# PLC-_-_-V2.net
KiCad netlist of a schematic drawn in Altium Designer
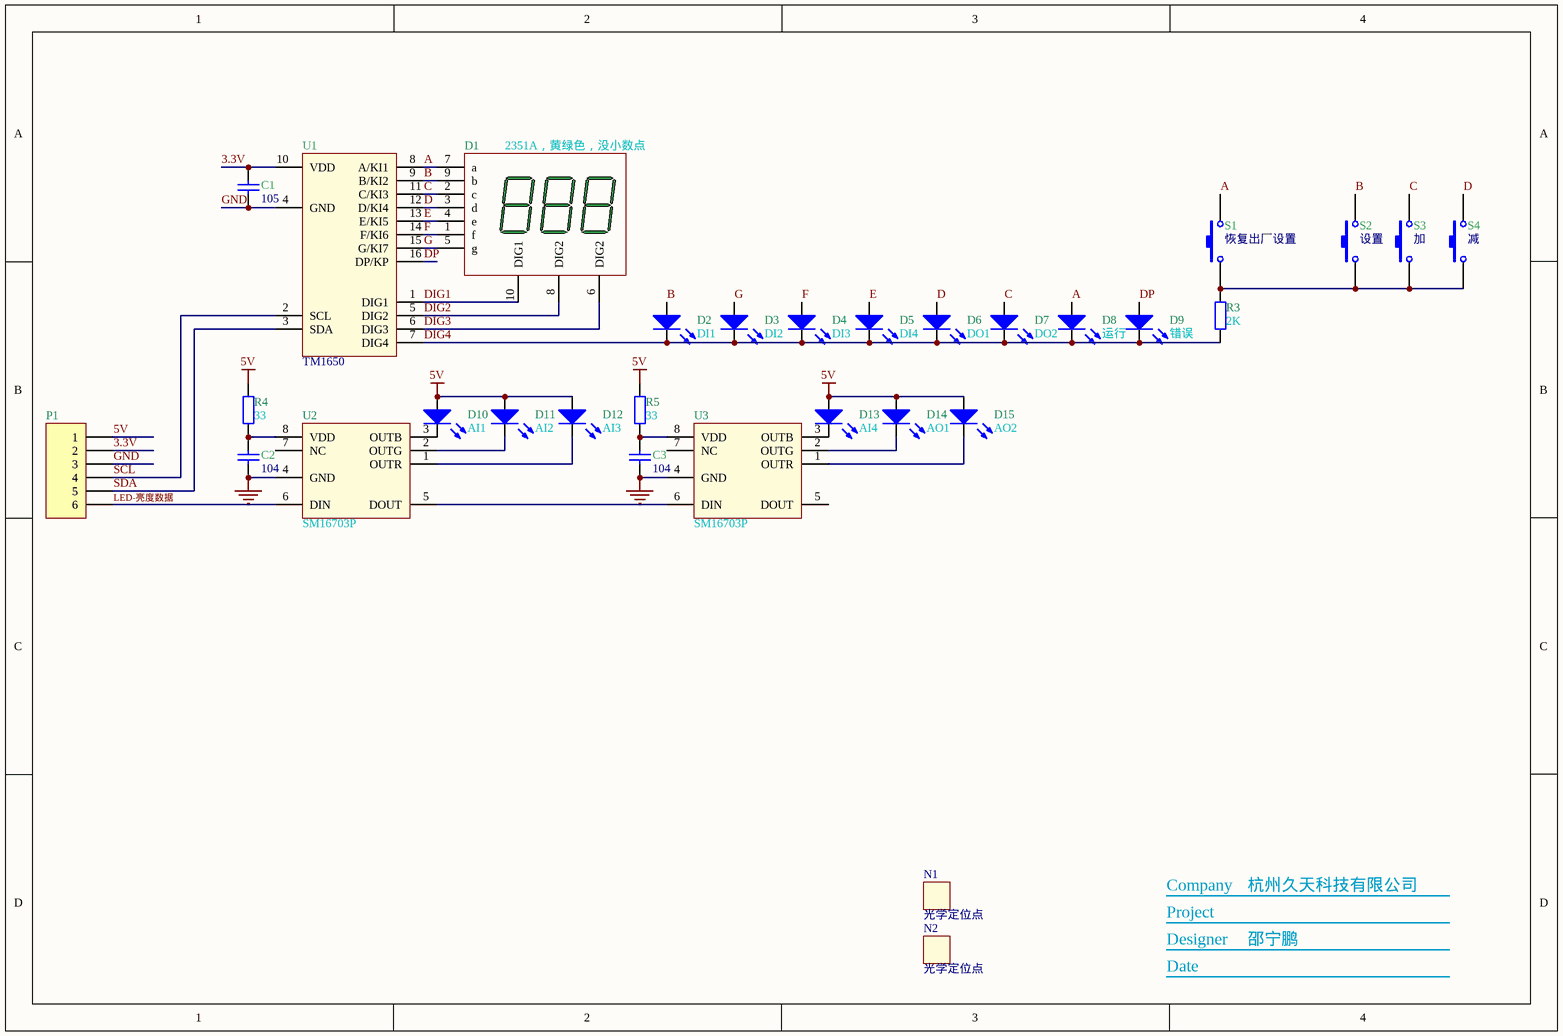
[diagram p0: PLC-无线通讯版-显示板-V2.SchDoc]

(export (version "E")
  (design (tool "Eeschema 10.0.6"))
  (components
    (comp (ref "C1")
      (value "105")
      (footprint "C-0603")
      (description "Capacitor")
      (fields (field (name "PUBLISHER") "Altium Limited"))
      (libsource (lib "元件2.0") (part "Cap"))
    )
    (comp (ref "C2")
      (value "104")
      (footprint "C-0603")
      (description "Capacitor")
      (fields (field (name "PUBLISHER") "Altium Limited"))
      (libsource (lib "元件2.0") (part "Cap"))
    )
    (comp (ref "C3")
      (value "104")
      (footprint "C-0603")
      (description "Capacitor")
      (fields (field (name "PUBLISHER") "Altium Limited"))
      (libsource (lib "元件2.0") (part "Cap"))
    )
    (comp (ref "D1")
      (value "2351A，黄绿色，没小数点")
      (footprint "3位0.25英寸")
      (libsource (lib "7显示屏-V1.0") (part "3位数码管-无点-2351A"))
    )
    (comp (ref "D2")
      (value "DI1")
      (footprint "LED-0603-GREEN")
      (fields (field (name "PUBLISHER") "Altium Limited"))
      (libsource (lib "4二极管-V1.1") (part "LED-0603-Blue"))
    )
    (comp (ref "D3")
      (value "DI2")
      (footprint "LED-0603-GREEN")
      (fields (field (name "PUBLISHER") "Altium Limited"))
      (libsource (lib "4二极管-V1.1") (part "LED-0603-Blue"))
    )
    (comp (ref "D4")
      (value "DI3")
      (footprint "LED-0603-GREEN")
      (fields (field (name "PUBLISHER") "Altium Limited"))
      (libsource (lib "4二极管-V1.1") (part "LED-0603-Blue"))
    )
    (comp (ref "D5")
      (value "DI4")
      (footprint "LED-0603-GREEN")
      (fields (field (name "PUBLISHER") "Altium Limited"))
      (libsource (lib "4二极管-V1.1") (part "LED-0603-Blue"))
    )
    (comp (ref "D6")
      (value "DO1")
      (footprint "LED-0603-GREEN")
      (fields (field (name "PUBLISHER") "Altium Limited"))
      (libsource (lib "4二极管-V1.1") (part "LED-0603-Blue"))
    )
    (comp (ref "D7")
      (value "DO2")
      (footprint "LED-0603-GREEN")
      (fields (field (name "PUBLISHER") "Altium Limited"))
      (libsource (lib "4二极管-V1.1") (part "LED-0603-Blue"))
    )
    (comp (ref "D8")
      (value "运行")
      (footprint "LED-0603-Blue")
      (fields (field (name "PUBLISHER") "Altium Limited"))
      (libsource (lib "4二极管-V1.1") (part "LED-0603-Blue"))
    )
    (comp (ref "D9")
      (value "错误")
      (footprint "LED-0603-Red")
      (fields (field (name "PUBLISHER") "Altium Limited"))
      (libsource (lib "4二极管-V1.1") (part "LED-0603-Blue"))
    )
    (comp (ref "D10")
      (value "AI1")
      (footprint "LED-0603-GREEN")
      (fields (field (name "PUBLISHER") "Altium Limited"))
      (libsource (lib "4二极管-V1.1") (part "LED-0603-Blue"))
    )
    (comp (ref "D11")
      (value "AI2")
      (footprint "LED-0603-GREEN")
      (fields (field (name "PUBLISHER") "Altium Limited"))
      (libsource (lib "4二极管-V1.1") (part "LED-0603-Blue"))
    )
    (comp (ref "D12")
      (value "AI3")
      (footprint "LED-0603-GREEN")
      (fields (field (name "PUBLISHER") "Altium Limited"))
      (libsource (lib "4二极管-V1.1") (part "LED-0603-Blue"))
    )
    (comp (ref "D13")
      (value "AI4")
      (footprint "LED-0603-GREEN")
      (fields (field (name "PUBLISHER") "Altium Limited"))
      (libsource (lib "4二极管-V1.1") (part "LED-0603-Blue"))
    )
    (comp (ref "D14")
      (value "AO1")
      (footprint "LED-0603-GREEN")
      (fields (field (name "PUBLISHER") "Altium Limited"))
      (libsource (lib "4二极管-V1.1") (part "LED-0603-Blue"))
    )
    (comp (ref "D15")
      (value "AO2")
      (footprint "LED-0603-GREEN")
      (fields (field (name "PUBLISHER") "Altium Limited"))
      (libsource (lib "4二极管-V1.1") (part "LED-0603-Blue"))
    )
    (comp (ref "N1") (value "光学定位点") (footprint "MARK-1mm-3mm") (libsource (lib "11其他元件-V1.0") (part "无引脚")))
    (comp (ref "N2") (value "光学定位点") (footprint "MARK-1mm-3mm") (libsource (lib "11其他元件-V1.0") (part "无引脚")))
    (comp (ref "P1")
      (value "~")
      (footprint "PH2.0-6AW")
      (description "Header, 6-Pin")
      (fields (field (name "PUBLISHER") "Altium Limited"))
      (libsource (lib "5排针-V1.0") (part "Header 6"))
    )
    (comp (ref "R3")
      (value "2K")
      (footprint "R-0603")
      (description "0603")
      (fields (field (name "PUBLISHER") "Altium Limited"))
      (libsource (lib "1电阻-V1.0") (part "Res2-0603"))
    )
    (comp (ref "R4")
      (value "33")
      (footprint "R-0603")
      (description "0603")
      (fields (field (name "PUBLISHER") "Altium Limited"))
      (libsource (lib "1电阻-V1.0") (part "Res2-0603"))
    )
    (comp (ref "R5")
      (value "33")
      (footprint "R-0603")
      (description "0603")
      (fields (field (name "PUBLISHER") "Altium Limited"))
      (libsource (lib "1电阻-V1.0") (part "Res2-0603"))
    )
    (comp (ref "S1")
      (value "恢复出厂设置")
      (footprint "SB-6*6*9.5_贴片")
      (description "SB-6*6*10")
      (fields (field (name "PUBLISHER") "Altium Limited"))
      (libsource (lib "开关-V1") (part "SB-6*6*9"))
    )
    (comp (ref "S2")
      (value "设置")
      (footprint "SB-6*6*9.5_贴片")
      (description "SB-6*6*10")
      (fields (field (name "PUBLISHER") "Altium Limited"))
      (libsource (lib "开关-V1") (part "SB-6*6*9"))
    )
    (comp (ref "S3")
      (value "加")
      (footprint "SB-6*6*9.5_贴片")
      (description "SB-6*6*10")
      (fields (field (name "PUBLISHER") "Altium Limited"))
      (libsource (lib "开关-V1") (part "SB-6*6*9"))
    )
    (comp (ref "S4")
      (value "减")
      (footprint "SB-6*6*9.5_贴片")
      (description "SB-6*6*10")
      (fields (field (name "PUBLISHER") "Altium Limited"))
      (libsource (lib "开关-V1") (part "SB-6*6*9"))
    )
    (comp (ref "U1")
      (value "TM1650")
      (footprint "SOP-16-M")
      (description "共阴数码管驱动器")
      (libsource (lib "8集成电路-V1.1") (part "TM1650"))
    )
    (comp (ref "U2")
      (value "SM16703P")
      (footprint "SOP-8-M")
      (libsource (lib "8集成电路-V1.1") (part "SM16703P"))
    )
    (comp (ref "U3")
      (value "SM16703P")
      (footprint "SOP-8-M")
      (libsource (lib "8集成电路-V1.1") (part "SM16703P"))
    )
  )
  (nets
    (net (code "1") (name "/3.3V") (class "Default")
      (node (ref "C1") (pin "2") (pinfunction "2_2") (pintype "passive"))
      (node (ref "P1") (pin "2") (pinfunction "2_2") (pintype "passive"))
      (node (ref "U1") (pin "10") (pinfunction "VDD_10") (pintype "passive"))
    )
    (net (code "2") (name "/A") (class "Default")
      (node (ref "D1") (pin "7") (pinfunction "a_7") (pintype "passive"))
      (node (ref "D8") (pin "1") (pinfunction "A_1") (pintype "passive"))
      (node (ref "S1") (pin "2") (pinfunction "2_2") (pintype "passive"))
      (node (ref "U1") (pin "8") (pinfunction "A/KI1_8") (pintype "passive"))
    )
    (net (code "3") (name "/B") (class "Default")
      (node (ref "D1") (pin "9") (pinfunction "b_9") (pintype "passive"))
      (node (ref "D2") (pin "1") (pinfunction "A_1") (pintype "passive"))
      (node (ref "S2") (pin "2") (pinfunction "2_2") (pintype "passive"))
      (node (ref "U1") (pin "9") (pinfunction "B/KI2_9") (pintype "passive"))
    )
    (net (code "4") (name "/C") (class "Default")
      (node (ref "D1") (pin "2") (pinfunction "c_2") (pintype "passive"))
      (node (ref "D7") (pin "1") (pinfunction "A_1") (pintype "passive"))
      (node (ref "S3") (pin "2") (pinfunction "2_2") (pintype "passive"))
      (node (ref "U1") (pin "11") (pinfunction "C/KI3_11") (pintype "passive"))
    )
    (net (code "5") (name "/D") (class "Default")
      (node (ref "D1") (pin "3") (pinfunction "d_3") (pintype "passive"))
      (node (ref "D6") (pin "1") (pinfunction "A_1") (pintype "passive"))
      (node (ref "S4") (pin "2") (pinfunction "2_2") (pintype "passive"))
      (node (ref "U1") (pin "12") (pinfunction "D/KI4_12") (pintype "passive"))
    )
    (net (code "6") (name "/DIG1") (class "Default")
      (node (ref "D1") (pin "10") (pinfunction "DIG1_10") (pintype "passive"))
      (node (ref "U1") (pin "1") (pinfunction "DIG1_1") (pintype "passive"))
    )
    (net (code "7") (name "/DIG2") (class "Default")
      (node (ref "D1") (pin "8") (pinfunction "DIG2_8") (pintype "passive"))
      (node (ref "U1") (pin "5") (pinfunction "DIG2_5") (pintype "passive"))
    )
    (net (code "8") (name "/DIG3") (class "Default")
      (node (ref "D1") (pin "6") (pinfunction "DIG2_6") (pintype "passive"))
      (node (ref "U1") (pin "6") (pinfunction "DIG3_6") (pintype "passive"))
    )
    (net (code "9") (name "/DIG4") (class "Default")
      (node (ref "D2") (pin "2") (pinfunction "K_2") (pintype "passive"))
      (node (ref "D3") (pin "2") (pinfunction "K_2") (pintype "passive"))
      (node (ref "D4") (pin "2") (pinfunction "K_2") (pintype "passive"))
      (node (ref "D5") (pin "2") (pinfunction "K_2") (pintype "passive"))
      (node (ref "D6") (pin "2") (pinfunction "K_2") (pintype "passive"))
      (node (ref "D7") (pin "2") (pinfunction "K_2") (pintype "passive"))
      (node (ref "D8") (pin "2") (pinfunction "K_2") (pintype "passive"))
      (node (ref "D9") (pin "2") (pinfunction "K_2") (pintype "passive"))
      (node (ref "R3") (pin "2") (pinfunction "2_2") (pintype "passive"))
      (node (ref "U1") (pin "7") (pinfunction "DIG4_7") (pintype "passive"))
    )
    (net (code "10") (name "/DP") (class "Default")
      (node (ref "D9") (pin "1") (pinfunction "A_1") (pintype "passive"))
      (node (ref "U1") (pin "16") (pinfunction "DP/KP_16") (pintype "passive"))
    )
    (net (code "11") (name "/E") (class "Default")
      (node (ref "D1") (pin "4") (pinfunction "e_4") (pintype "passive"))
      (node (ref "D5") (pin "1") (pinfunction "A_1") (pintype "passive"))
      (node (ref "U1") (pin "13") (pinfunction "E/KI5_13") (pintype "passive"))
    )
    (net (code "12") (name "/F") (class "Default")
      (node (ref "D1") (pin "1") (pinfunction "f_1") (pintype "passive"))
      (node (ref "D4") (pin "1") (pinfunction "A_1") (pintype "passive"))
      (node (ref "U1") (pin "14") (pinfunction "F/KI6_14") (pintype "passive"))
    )
    (net (code "13") (name "/G") (class "Default")
      (node (ref "D1") (pin "5") (pinfunction "g_5") (pintype "passive"))
      (node (ref "D3") (pin "1") (pinfunction "A_1") (pintype "passive"))
      (node (ref "U1") (pin "15") (pinfunction "G/KI7_15") (pintype "passive"))
    )
    (net (code "14") (name "/LED-亮度数据") (class "Default")
      (node (ref "P1") (pin "6") (pinfunction "6_6") (pintype "passive"))
      (node (ref "U2") (pin "6") (pinfunction "DIN_6") (pintype "passive"))
    )
    (net (code "15") (name "/SCL") (class "Default")
      (node (ref "P1") (pin "4") (pinfunction "4_4") (pintype "passive"))
      (node (ref "U1") (pin "2") (pinfunction "SCL_2") (pintype "passive"))
    )
    (net (code "16") (name "/SDA") (class "Default")
      (node (ref "P1") (pin "5") (pinfunction "5_5") (pintype "passive"))
      (node (ref "U1") (pin "3") (pinfunction "SDA_3") (pintype "passive"))
    )
    (net (code "17") (name "5V") (class "Default")
      (node (ref "D10") (pin "1") (pinfunction "A_1") (pintype "passive"))
      (node (ref "D11") (pin "1") (pinfunction "A_1") (pintype "passive"))
      (node (ref "D12") (pin "1") (pinfunction "A_1") (pintype "passive"))
      (node (ref "D13") (pin "1") (pinfunction "A_1") (pintype "passive"))
      (node (ref "D14") (pin "1") (pinfunction "A_1") (pintype "passive"))
      (node (ref "D15") (pin "1") (pinfunction "A_1") (pintype "passive"))
      (node (ref "P1") (pin "1") (pinfunction "1_1") (pintype "passive"))
      (node (ref "R4") (pin "1") (pinfunction "1_1") (pintype "passive"))
      (node (ref "R5") (pin "1") (pinfunction "1_1") (pintype "passive"))
    )
    (net (code "18") (name "GND") (class "Default")
      (node (ref "C1") (pin "1") (pinfunction "1_1") (pintype "passive"))
      (node (ref "C2") (pin "1") (pinfunction "1_1") (pintype "passive"))
      (node (ref "C3") (pin "1") (pinfunction "1_1") (pintype "passive"))
      (node (ref "P1") (pin "3") (pinfunction "3_3") (pintype "passive"))
      (node (ref "U1") (pin "4") (pinfunction "GND_4") (pintype "passive"))
      (node (ref "U2") (pin "4") (pinfunction "GND_4") (pintype "passive"))
      (node (ref "U3") (pin "4") (pinfunction "GND_4") (pintype "passive"))
    )
    (net (code "19") (name "Net-(D10-K)") (class "Default")
      (node (ref "D10") (pin "2") (pinfunction "K_2") (pintype "passive"))
      (node (ref "U2") (pin "3") (pinfunction "OUTB_3") (pintype "passive"))
    )
    (net (code "20") (name "Net-(D11-K)") (class "Default")
      (node (ref "D11") (pin "2") (pinfunction "K_2") (pintype "passive"))
      (node (ref "U2") (pin "2") (pinfunction "OUTG_2") (pintype "passive"))
    )
    (net (code "21") (name "Net-(D12-K)") (class "Default")
      (node (ref "D12") (pin "2") (pinfunction "K_2") (pintype "passive"))
      (node (ref "U2") (pin "1") (pinfunction "OUTR_1") (pintype "passive"))
    )
    (net (code "22") (name "Net-(D13-K)") (class "Default")
      (node (ref "D13") (pin "2") (pinfunction "K_2") (pintype "passive"))
      (node (ref "U3") (pin "3") (pinfunction "OUTB_3") (pintype "passive"))
    )
    (net (code "23") (name "Net-(D14-K)") (class "Default")
      (node (ref "D14") (pin "2") (pinfunction "K_2") (pintype "passive"))
      (node (ref "U3") (pin "2") (pinfunction "OUTG_2") (pintype "passive"))
    )
    (net (code "24") (name "Net-(D15-K)") (class "Default")
      (node (ref "D15") (pin "2") (pinfunction "K_2") (pintype "passive"))
      (node (ref "U3") (pin "1") (pinfunction "OUTR_1") (pintype "passive"))
    )
    (net (code "25") (name "Net-(R3-Pad1)") (class "Default")
      (node (ref "R3") (pin "1") (pinfunction "1_1") (pintype "passive"))
      (node (ref "S1") (pin "1") (pinfunction "1_1") (pintype "passive"))
      (node (ref "S2") (pin "1") (pinfunction "1_1") (pintype "passive"))
      (node (ref "S3") (pin "1") (pinfunction "1_1") (pintype "passive"))
      (node (ref "S4") (pin "1") (pinfunction "1_1") (pintype "passive"))
    )
    (net (code "26") (name "Net-(U2-DOUT)") (class "Default")
      (node (ref "U2") (pin "5") (pinfunction "DOUT_5") (pintype "passive"))
      (node (ref "U3") (pin "6") (pinfunction "DIN_6") (pintype "passive"))
    )
    (net (code "27") (name "Net-(U2-VDD)") (class "Default")
      (node (ref "C2") (pin "2") (pinfunction "2_2") (pintype "passive"))
      (node (ref "R4") (pin "2") (pinfunction "2_2") (pintype "passive"))
      (node (ref "U2") (pin "8") (pinfunction "VDD_8") (pintype "passive"))
    )
    (net (code "28") (name "Net-(U3-VDD)") (class "Default")
      (node (ref "C3") (pin "2") (pinfunction "2_2") (pintype "passive"))
      (node (ref "R5") (pin "2") (pinfunction "2_2") (pintype "passive"))
      (node (ref "U3") (pin "8") (pinfunction "VDD_8") (pintype "passive"))
    )
    (net (code "29") (name "unconnected-(U2-NC-Pad7)") (class "Default")
      (node (ref "U2") (pin "7") (pinfunction "NC_7") (pintype "passive"))
    )
    (net (code "30") (name "unconnected-(U3-DOUT-Pad5)") (class "Default")
      (node (ref "U3") (pin "5") (pinfunction "DOUT_5") (pintype "passive"))
    )
    (net (code "31") (name "unconnected-(U3-NC-Pad7)") (class "Default")
      (node (ref "U3") (pin "7") (pinfunction "NC_7") (pintype "passive"))
    )
  )
)
